# Peripherals.net
KiCad netlist of a schematic drawn in Altium Designer
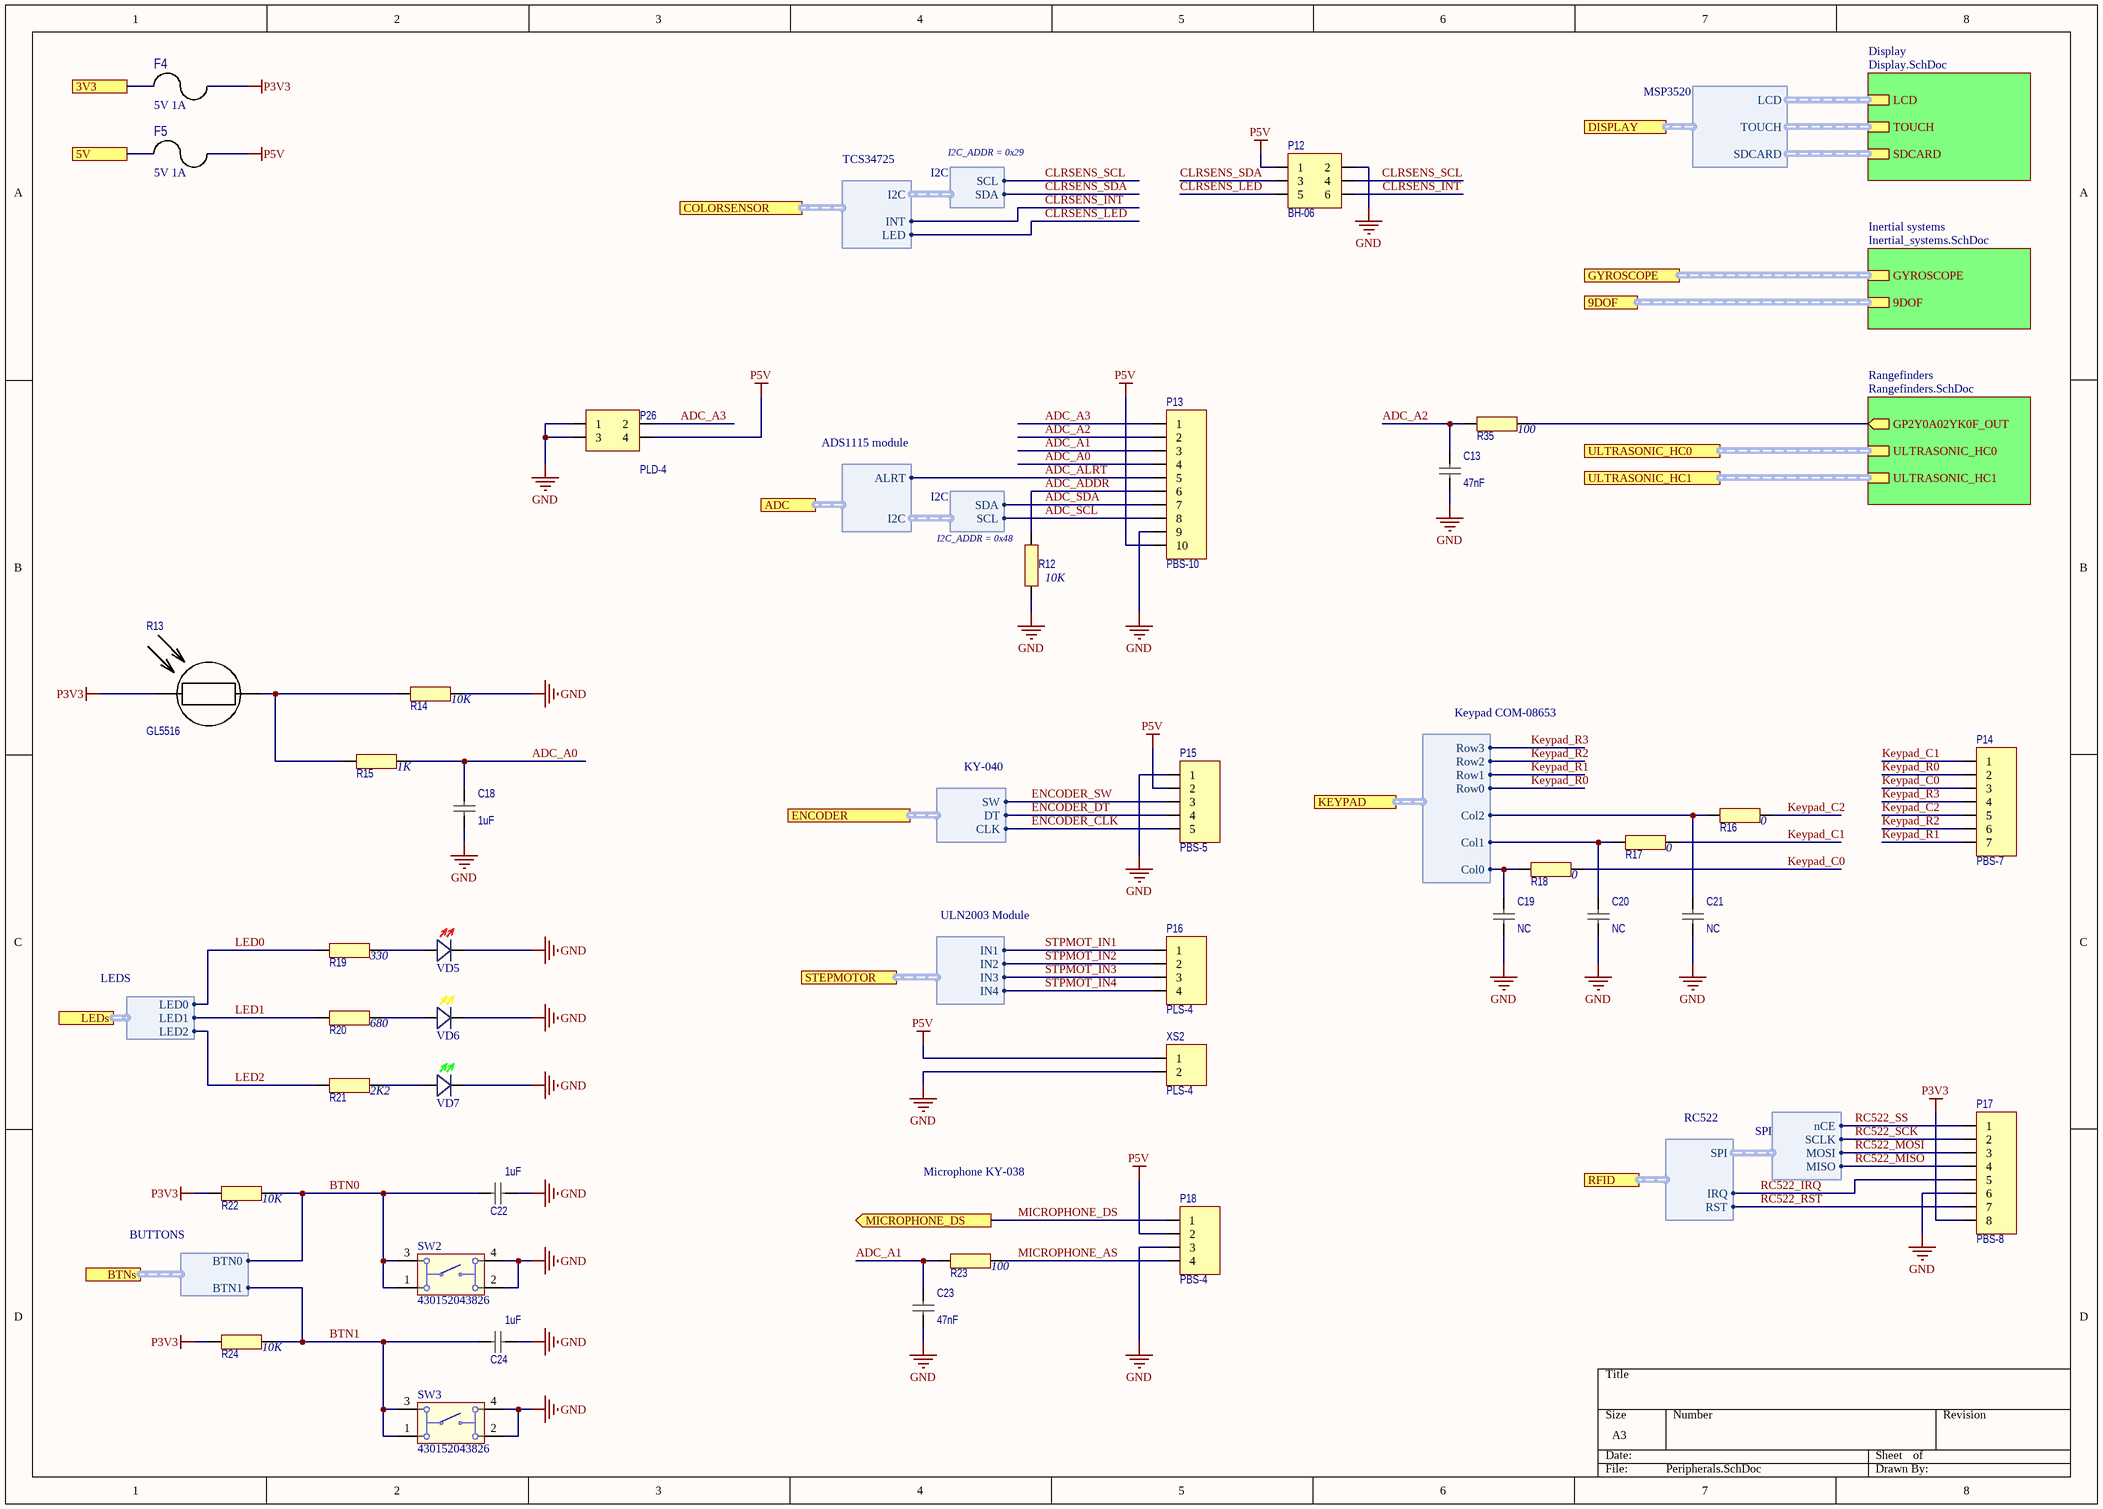
[diagram p0: Peripherals.SchDoc]

(export (version "E")
  (design (tool "Eeschema 10.0.6"))
  (components
    (comp (ref "C13")
      (value "47nF")
      (footprint "C0805")
      (fields (field (name "TOLERANCE") "%") (field (name "VOLTAGE") "B") (field (name "Comment") "C0805"))
      (libsource (lib "my_AP_lib_sch") (part "C0805"))
    )
    (comp (ref "C18")
      (value "1uF")
      (footprint "C0805")
      (fields (field (name "TOLERANCE") "%") (field (name "VOLTAGE") "B") (field (name "Comment") "C0805"))
      (libsource (lib "my_AP_lib_sch") (part "C0805"))
    )
    (comp (ref "C19")
      (value "NC")
      (footprint "C0805")
      (fields (field (name "TOLERANCE") "%") (field (name "VOLTAGE") "B") (field (name "Comment") "C0805"))
      (libsource (lib "my_AP_lib_sch") (part "C0805"))
    )
    (comp (ref "C20")
      (value "NC")
      (footprint "C0805")
      (fields (field (name "TOLERANCE") "%") (field (name "VOLTAGE") "B") (field (name "Comment") "C0805"))
      (libsource (lib "my_AP_lib_sch") (part "C0805"))
    )
    (comp (ref "C21")
      (value "NC")
      (footprint "C0805")
      (fields (field (name "TOLERANCE") "%") (field (name "VOLTAGE") "B") (field (name "Comment") "C0805"))
      (libsource (lib "my_AP_lib_sch") (part "C0805"))
    )
    (comp (ref "C22")
      (value "1uF")
      (footprint "C0805")
      (fields (field (name "TOLERANCE") "%") (field (name "VOLTAGE") "B") (field (name "Comment") "C0805"))
      (libsource (lib "my_AP_lib_sch") (part "C0805"))
    )
    (comp (ref "C23")
      (value "47nF")
      (footprint "C0805")
      (fields (field (name "TOLERANCE") "%") (field (name "VOLTAGE") "B") (field (name "Comment") "C0805"))
      (libsource (lib "my_AP_lib_sch") (part "C0805"))
    )
    (comp (ref "C24")
      (value "1uF")
      (footprint "C0805")
      (fields (field (name "TOLERANCE") "%") (field (name "VOLTAGE") "B") (field (name "Comment") "C0805"))
      (libsource (lib "my_AP_lib_sch") (part "C0805"))
    )
    (comp (ref "F4")
      (value "5V 1A")
      (footprint "FUSC6127X269N")
      (description "045303.5MR")
      (libsource (lib "my_AP_lib_sch") (part "F"))
    )
    (comp (ref "F5")
      (value "5V 1A")
      (footprint "FUSC6127X269N")
      (description "045303.5MR")
      (libsource (lib "my_AP_lib_sch") (part "F"))
    )
    (comp (ref "P12") (value "BH-06") (footprint "BH-06") (libsource (lib "my_AP_lib_sch") (part "BH-06")))
    (comp (ref "P13") (value "PBS-10") (footprint "PBS-10") (libsource (lib "my_AP_lib_sch") (part "PBS-10")))
    (comp (ref "P14") (value "PBS-7") (footprint "PBS-7") (libsource (lib "my_AP_lib_sch") (part "PBS-7")))
    (comp (ref "P15") (value "PBS-5") (footprint "PBS-5") (libsource (lib "my_AP_lib_sch") (part "PBS-5")))
    (comp (ref "P16") (value "PLS-4") (footprint "PLS-4") (libsource (lib "my_AP_lib_sch") (part "PLS-4")))
    (comp (ref "P17") (value "PBS-8") (footprint "PBS-8") (libsource (lib "my_AP_lib_sch") (part "PBS-8")))
    (comp (ref "P18") (value "PBS-4") (footprint "PBS-4") (libsource (lib "my_AP_lib_sch") (part "PBS-4")))
    (comp (ref "P26") (value "PLD-4") (footprint "PLD-4") (libsource (lib "my_AP_lib_sch") (part "PLD-4")))
    (comp (ref "R12")
      (value "10K")
      (footprint "R0805")
      (fields (field (name "Comment") "R0805"))
      (libsource (lib "") (part "R0805_1"))
    )
    (comp (ref "R13")
      (value "GL5516")
      (footprint "GL5516")
      (libsource (lib "my_AP_lib_sch") (part "Light Sensor"))
    )
    (comp (ref "R14")
      (value "10K")
      (footprint "R0805")
      (fields (field (name "Comment") "R0805"))
      (libsource (lib "my_AP_lib_sch") (part "R0805"))
    )
    (comp (ref "R15")
      (value "1K")
      (footprint "R0805")
      (fields (field (name "Comment") "R0805"))
      (libsource (lib "my_AP_lib_sch") (part "R0805"))
    )
    (comp (ref "R16")
      (value "0")
      (footprint "R0805")
      (fields (field (name "Comment") "R0805"))
      (libsource (lib "my_AP_lib_sch") (part "R0805"))
    )
    (comp (ref "R17")
      (value "0")
      (footprint "R0805")
      (fields (field (name "Comment") "R0805"))
      (libsource (lib "my_AP_lib_sch") (part "R0805"))
    )
    (comp (ref "R18")
      (value "0")
      (footprint "R0805")
      (fields (field (name "Comment") "R0805"))
      (libsource (lib "my_AP_lib_sch") (part "R0805"))
    )
    (comp (ref "R19")
      (value "330")
      (footprint "R0805")
      (fields (field (name "Comment") "R0805"))
      (libsource (lib "my_AP_lib_sch") (part "R0805"))
    )
    (comp (ref "R20")
      (value "680")
      (footprint "R0805")
      (fields (field (name "Comment") "R0805"))
      (libsource (lib "my_AP_lib_sch") (part "R0805"))
    )
    (comp (ref "R21")
      (value "2K2")
      (footprint "R0805")
      (fields (field (name "Comment") "R0805"))
      (libsource (lib "my_AP_lib_sch") (part "R0805"))
    )
    (comp (ref "R22")
      (value "10K")
      (footprint "R0805")
      (fields (field (name "Comment") "R0805"))
      (libsource (lib "my_AP_lib_sch") (part "R0805"))
    )
    (comp (ref "R23")
      (value "100")
      (footprint "R0805")
      (fields (field (name "Comment") "R0805"))
      (libsource (lib "my_AP_lib_sch") (part "R0805"))
    )
    (comp (ref "R24")
      (value "10K")
      (footprint "R0805")
      (fields (field (name "Comment") "R0805"))
      (libsource (lib "my_AP_lib_sch") (part "R0805"))
    )
    (comp (ref "R35")
      (value "100")
      (footprint "R0805")
      (fields (field (name "Comment") "R0805"))
      (libsource (lib "my_AP_lib_sch") (part "R0805"))
    )
    (comp (ref "SW2")
      (value "430152043826")
      (footprint "430152043826")
      (description "WS-TASV SMD Tact Switch 6X6 mm")
      (libsource (lib "WS-TASV SMD Tact Switch 6X6 mm") (part "430152043826"))
    )
    (comp (ref "SW3")
      (value "430152043826")
      (footprint "430152043826")
      (description "WS-TASV SMD Tact Switch 6X6 mm")
      (libsource (lib "WS-TASV SMD Tact Switch 6X6 mm") (part "430152043826"))
    )
    (comp (ref "VD5")
      (value "TO-1608BC-MRE")
      (footprint "TO-1608BC-MRE")
      (description "LED SMD 1608 112мКд, 120°, 630нМ (Ultra Bright Red)")
      (libsource (lib "my_AP_lib_sch") (part "TO-1608BC-MRE"))
    )
    (comp (ref "VD6")
      (value "TO-1608BC-MYF")
      (footprint "TO-1608BC-MYF")
      (description "LED SMD 1608 247мКд, 120°, 592нМ (High Bright Yellow)")
      (libsource (lib "my_AP_lib_sch") (part "TO-1608BC-MYF"))
    )
    (comp (ref "VD7")
      (value "TO-1608BC-PG")
      (footprint "TO-1608BC-PG")
      (description "LED SMD 1608 705мКд, 120°, 525нМ (Pure Green)")
      (libsource (lib "my_AP_lib_sch") (part "TO-1608BC-PG"))
    )
    (comp (ref "XS2") (value "PLS-4") (footprint "PLS-2") (libsource (lib "my_AP_lib_sch") (part "PLS-2")))
  )
  (nets
    (net (code "24") (name "/3V3") (class "Default")
      (node (ref "F4") (pin "1") (pinfunction "1_1") (pintype "passive"))
    )
    (net (code "25") (name "/5V") (class "Default")
      (node (ref "F5") (pin "1") (pinfunction "1_1") (pintype "passive"))
    )
    (net (code "27") (name "/ADC_A0") (class "Default")
      (node (ref "C18") (pin "2") (pinfunction "2_2") (pintype "passive"))
      (node (ref "P13") (pin "4") (pinfunction "4_4") (pintype "passive"))
      (node (ref "R15") (pin "1") (pinfunction "1_1") (pintype "passive"))
    )
    (net (code "28") (name "/ADC_A1") (class "Default")
      (node (ref "C23") (pin "2") (pinfunction "2_2") (pintype "passive"))
      (node (ref "P13") (pin "3") (pinfunction "3_3") (pintype "passive"))
      (node (ref "R23") (pin "2") (pinfunction "2_2") (pintype "passive"))
    )
    (net (code "29") (name "/ADC_A2") (class "Default")
      (node (ref "C13") (pin "2") (pinfunction "2_2") (pintype "passive"))
      (node (ref "P13") (pin "2") (pinfunction "2_2") (pintype "passive"))
      (node (ref "R35") (pin "2") (pinfunction "2_2") (pintype "passive"))
    )
    (net (code "30") (name "/ADC_A3") (class "Default")
      (node (ref "P13") (pin "1") (pinfunction "1_1") (pintype "passive"))
      (node (ref "P26") (pin "2") (pinfunction "2_2") (pintype "passive"))
    )
    (net (code "31") (name "/ADC_ADDR") (class "Default")
      (node (ref "P13") (pin "6") (pinfunction "6_6") (pintype "passive"))
      (node (ref "R12") (pin "1") (pinfunction "1_1") (pintype "passive"))
    )
    (net (code "32") (name "/ADC_ALRT") (class "Default")
      (node (ref "P13") (pin "5") (pinfunction "5_5") (pintype "passive"))
    )
    (net (code "33") (name "/ADC_SCL") (class "Default")
      (node (ref "P13") (pin "8") (pinfunction "8_8") (pintype "passive"))
    )
    (net (code "34") (name "/ADC_SDA") (class "Default")
      (node (ref "P13") (pin "7") (pinfunction "7_7") (pintype "passive"))
    )
    (net (code "36") (name "/BTN0") (class "Default")
      (node (ref "C22") (pin "2") (pinfunction "2_2") (pintype "passive"))
      (node (ref "R22") (pin "1") (pinfunction "1_1") (pintype "passive"))
      (node (ref "SW2") (pin "1") (pinfunction "1_1") (pintype "passive"))
      (node (ref "SW2") (pin "3") (pinfunction "3_3") (pintype "passive"))
    )
    (net (code "37") (name "/BTN1") (class "Default")
      (node (ref "C24") (pin "2") (pinfunction "2_2") (pintype "passive"))
      (node (ref "R24") (pin "1") (pinfunction "1_1") (pintype "passive"))
      (node (ref "SW3") (pin "1") (pinfunction "1_1") (pintype "passive"))
      (node (ref "SW3") (pin "3") (pinfunction "3_3") (pintype "passive"))
    )
    (net (code "38") (name "/CLRSENS_INT") (class "Default")
      (node (ref "P12") (pin "6") (pinfunction "6_6") (pintype "passive"))
    )
    (net (code "39") (name "/CLRSENS_LED") (class "Default")
      (node (ref "P12") (pin "5") (pinfunction "5_5") (pintype "passive"))
    )
    (net (code "40") (name "/CLRSENS_SCL") (class "Default")
      (node (ref "P12") (pin "4") (pinfunction "4_4") (pintype "passive"))
    )
    (net (code "41") (name "/CLRSENS_SDA") (class "Default")
      (node (ref "P12") (pin "3") (pinfunction "3_3") (pintype "passive"))
    )
    (net (code "44") (name "/ENCODER_CLK") (class "Default")
      (node (ref "P15") (pin "5") (pinfunction "5_5") (pintype "passive"))
    )
    (net (code "45") (name "/ENCODER_DT") (class "Default")
      (node (ref "P15") (pin "4") (pinfunction "4_4") (pintype "passive"))
    )
    (net (code "46") (name "/ENCODER_SW") (class "Default")
      (node (ref "P15") (pin "3") (pinfunction "3_3") (pintype "passive"))
    )
    (net (code "47") (name "/GP2Y0A02YK0F_OUT") (class "Default")
      (node (ref "R35") (pin "1") (pinfunction "1_1") (pintype "passive"))
    )
    (net (code "49") (name "/Keypad_C0") (class "Default")
      (node (ref "P14") (pin "3") (pinfunction "3_3") (pintype "passive"))
      (node (ref "R18") (pin "1") (pinfunction "1_1") (pintype "passive"))
    )
    (net (code "50") (name "/Keypad_C1") (class "Default")
      (node (ref "P14") (pin "1") (pinfunction "1_1") (pintype "passive"))
      (node (ref "R17") (pin "1") (pinfunction "1_1") (pintype "passive"))
    )
    (net (code "51") (name "/Keypad_C2") (class "Default")
      (node (ref "P14") (pin "5") (pinfunction "5_5") (pintype "passive"))
      (node (ref "R16") (pin "1") (pinfunction "1_1") (pintype "passive"))
    )
    (net (code "52") (name "/Keypad_R0") (class "Default")
      (node (ref "P14") (pin "2") (pinfunction "2_2") (pintype "passive"))
    )
    (net (code "53") (name "/Keypad_R1") (class "Default")
      (node (ref "P14") (pin "7") (pinfunction "7_7") (pintype "passive"))
    )
    (net (code "54") (name "/Keypad_R2") (class "Default")
      (node (ref "P14") (pin "6") (pinfunction "6_6") (pintype "passive"))
    )
    (net (code "55") (name "/Keypad_R3") (class "Default")
      (node (ref "P14") (pin "4") (pinfunction "4_4") (pintype "passive"))
    )
    (net (code "57") (name "/LED0") (class "Default")
      (node (ref "R19") (pin "2") (pinfunction "2_2") (pintype "passive"))
    )
    (net (code "58") (name "/LED1") (class "Default")
      (node (ref "R20") (pin "2") (pinfunction "2_2") (pintype "passive"))
    )
    (net (code "59") (name "/LED2") (class "Default")
      (node (ref "R21") (pin "2") (pinfunction "2_2") (pintype "passive"))
    )
    (net (code "60") (name "/MICROPHONE_AS") (class "Default")
      (node (ref "P18") (pin "4") (pinfunction "4_4") (pintype "passive"))
      (node (ref "R23") (pin "1") (pinfunction "1_1") (pintype "passive"))
    )
    (net (code "61") (name "/MICROPHONE_DS") (class "Default")
      (node (ref "P18") (pin "1") (pinfunction "1_1") (pintype "passive"))
    )
    (net (code "62") (name "/RC522_IRQ") (class "Default")
      (node (ref "P17") (pin "5") (pinfunction "5_5") (pintype "passive"))
    )
    (net (code "63") (name "/RC522_MISO") (class "Default")
      (node (ref "P17") (pin "4") (pinfunction "4_4") (pintype "passive"))
    )
    (net (code "64") (name "/RC522_MOSI") (class "Default")
      (node (ref "P17") (pin "3") (pinfunction "3_3") (pintype "passive"))
    )
    (net (code "65") (name "/RC522_RST") (class "Default")
      (node (ref "P17") (pin "7") (pinfunction "7_7") (pintype "passive"))
    )
    (net (code "66") (name "/RC522_SCK") (class "Default")
      (node (ref "P17") (pin "2") (pinfunction "2_2") (pintype "passive"))
    )
    (net (code "67") (name "/RC522_SS") (class "Default")
      (node (ref "P17") (pin "1") (pinfunction "1_1") (pintype "passive"))
    )
    (net (code "69") (name "/STPMOT_IN1") (class "Default")
      (node (ref "P16") (pin "1") (pinfunction "1_1") (pintype "passive"))
    )
    (net (code "70") (name "/STPMOT_IN2") (class "Default")
      (node (ref "P16") (pin "2") (pinfunction "2_2") (pintype "passive"))
    )
    (net (code "71") (name "/STPMOT_IN3") (class "Default")
      (node (ref "P16") (pin "3") (pinfunction "3_3") (pintype "passive"))
    )
    (net (code "72") (name "/STPMOT_IN4") (class "Default")
      (node (ref "P16") (pin "4") (pinfunction "4_4") (pintype "passive"))
    )
    (net (code "85") (name "GND") (class "Default")
      (node (ref "C13") (pin "1") (pinfunction "1_1") (pintype "passive"))
      (node (ref "C18") (pin "1") (pinfunction "1_1") (pintype "passive"))
      (node (ref "C19") (pin "1") (pinfunction "1_1") (pintype "passive"))
      (node (ref "C20") (pin "1") (pinfunction "1_1") (pintype "passive"))
      (node (ref "C21") (pin "1") (pinfunction "1_1") (pintype "passive"))
      (node (ref "C22") (pin "1") (pinfunction "1_1") (pintype "passive"))
      (node (ref "C23") (pin "1") (pinfunction "1_1") (pintype "passive"))
      (node (ref "C24") (pin "1") (pinfunction "1_1") (pintype "passive"))
      (node (ref "P12") (pin "2") (pinfunction "2_2") (pintype "passive"))
      (node (ref "P13") (pin "9") (pinfunction "9_9") (pintype "passive"))
      (node (ref "P15") (pin "1") (pinfunction "1_1") (pintype "passive"))
      (node (ref "P17") (pin "6") (pinfunction "6_6") (pintype "passive"))
      (node (ref "P18") (pin "3") (pinfunction "3_3") (pintype "passive"))
      (node (ref "P26") (pin "1") (pinfunction "1_1") (pintype "passive"))
      (node (ref "P26") (pin "3") (pinfunction "3_3") (pintype "passive"))
      (node (ref "R12") (pin "2") (pinfunction "2_2") (pintype "passive"))
      (node (ref "R14") (pin "1") (pinfunction "1_1") (pintype "passive"))
      (node (ref "SW2") (pin "2") (pinfunction "2_2") (pintype "passive"))
      (node (ref "SW2") (pin "4") (pinfunction "4_4") (pintype "passive"))
      (node (ref "SW3") (pin "2") (pinfunction "2_2") (pintype "passive"))
      (node (ref "SW3") (pin "4") (pinfunction "4_4") (pintype "passive"))
      (node (ref "VD5") (pin "-") (pinfunction "-_-") (pintype "passive"))
      (node (ref "VD6") (pin "-") (pinfunction "-_-") (pintype "passive"))
      (node (ref "VD7") (pin "-") (pinfunction "-_-") (pintype "passive"))
      (node (ref "XS2") (pin "2") (pinfunction "2_2") (pintype "passive"))
    )
    (net (code "86") (name "Net-(C19-Pad2)") (class "Default")
      (node (ref "C19") (pin "2") (pinfunction "2_2") (pintype "passive"))
      (node (ref "R18") (pin "2") (pinfunction "2_2") (pintype "passive"))
    )
    (net (code "87") (name "Net-(C20-Pad2)") (class "Default")
      (node (ref "C20") (pin "2") (pinfunction "2_2") (pintype "passive"))
      (node (ref "R17") (pin "2") (pinfunction "2_2") (pintype "passive"))
    )
    (net (code "88") (name "Net-(C21-Pad2)") (class "Default")
      (node (ref "C21") (pin "2") (pinfunction "2_2") (pintype "passive"))
      (node (ref "R16") (pin "2") (pinfunction "2_2") (pintype "passive"))
    )
    (net (code "89") (name "Net-(R13-Pad2)") (class "Default")
      (node (ref "R13") (pin "2") (pinfunction "2_2") (pintype "passive"))
      (node (ref "R14") (pin "2") (pinfunction "2_2") (pintype "passive"))
      (node (ref "R15") (pin "2") (pinfunction "2_2") (pintype "passive"))
    )
    (net (code "90") (name "Net-(R19-Pad1)") (class "Default")
      (node (ref "R19") (pin "1") (pinfunction "1_1") (pintype "passive"))
      (node (ref "VD5") (pin "+") (pinfunction "+_+") (pintype "passive"))
    )
    (net (code "91") (name "Net-(R20-Pad1)") (class "Default")
      (node (ref "R20") (pin "1") (pinfunction "1_1") (pintype "passive"))
      (node (ref "VD6") (pin "+") (pinfunction "+_+") (pintype "passive"))
    )
    (net (code "92") (name "Net-(R21-Pad1)") (class "Default")
      (node (ref "R21") (pin "1") (pinfunction "1_1") (pintype "passive"))
      (node (ref "VD7") (pin "+") (pinfunction "+_+") (pintype "passive"))
    )
    (net (code "93") (name "P3V3") (class "Default")
      (node (ref "F4") (pin "2") (pinfunction "2_2") (pintype "passive"))
      (node (ref "P17") (pin "8") (pinfunction "8_8") (pintype "passive"))
      (node (ref "R13") (pin "1") (pinfunction "1_1") (pintype "passive"))
      (node (ref "R22") (pin "2") (pinfunction "2_2") (pintype "passive"))
      (node (ref "R24") (pin "2") (pinfunction "2_2") (pintype "passive"))
    )
    (net (code "94") (name "P5V") (class "Default")
      (node (ref "F5") (pin "2") (pinfunction "2_2") (pintype "passive"))
      (node (ref "P12") (pin "1") (pinfunction "1_1") (pintype "passive"))
      (node (ref "P13") (pin "10") (pinfunction "10_10") (pintype "passive"))
      (node (ref "P15") (pin "2") (pinfunction "2_2") (pintype "passive"))
      (node (ref "P18") (pin "2") (pinfunction "2_2") (pintype "passive"))
      (node (ref "P26") (pin "4") (pinfunction "4_4") (pintype "passive"))
      (node (ref "XS2") (pin "1") (pinfunction "1_1") (pintype "passive"))
    )
  )
)
